# Sheet1.net
KiCad netlist of a schematic drawn in Altium Designer
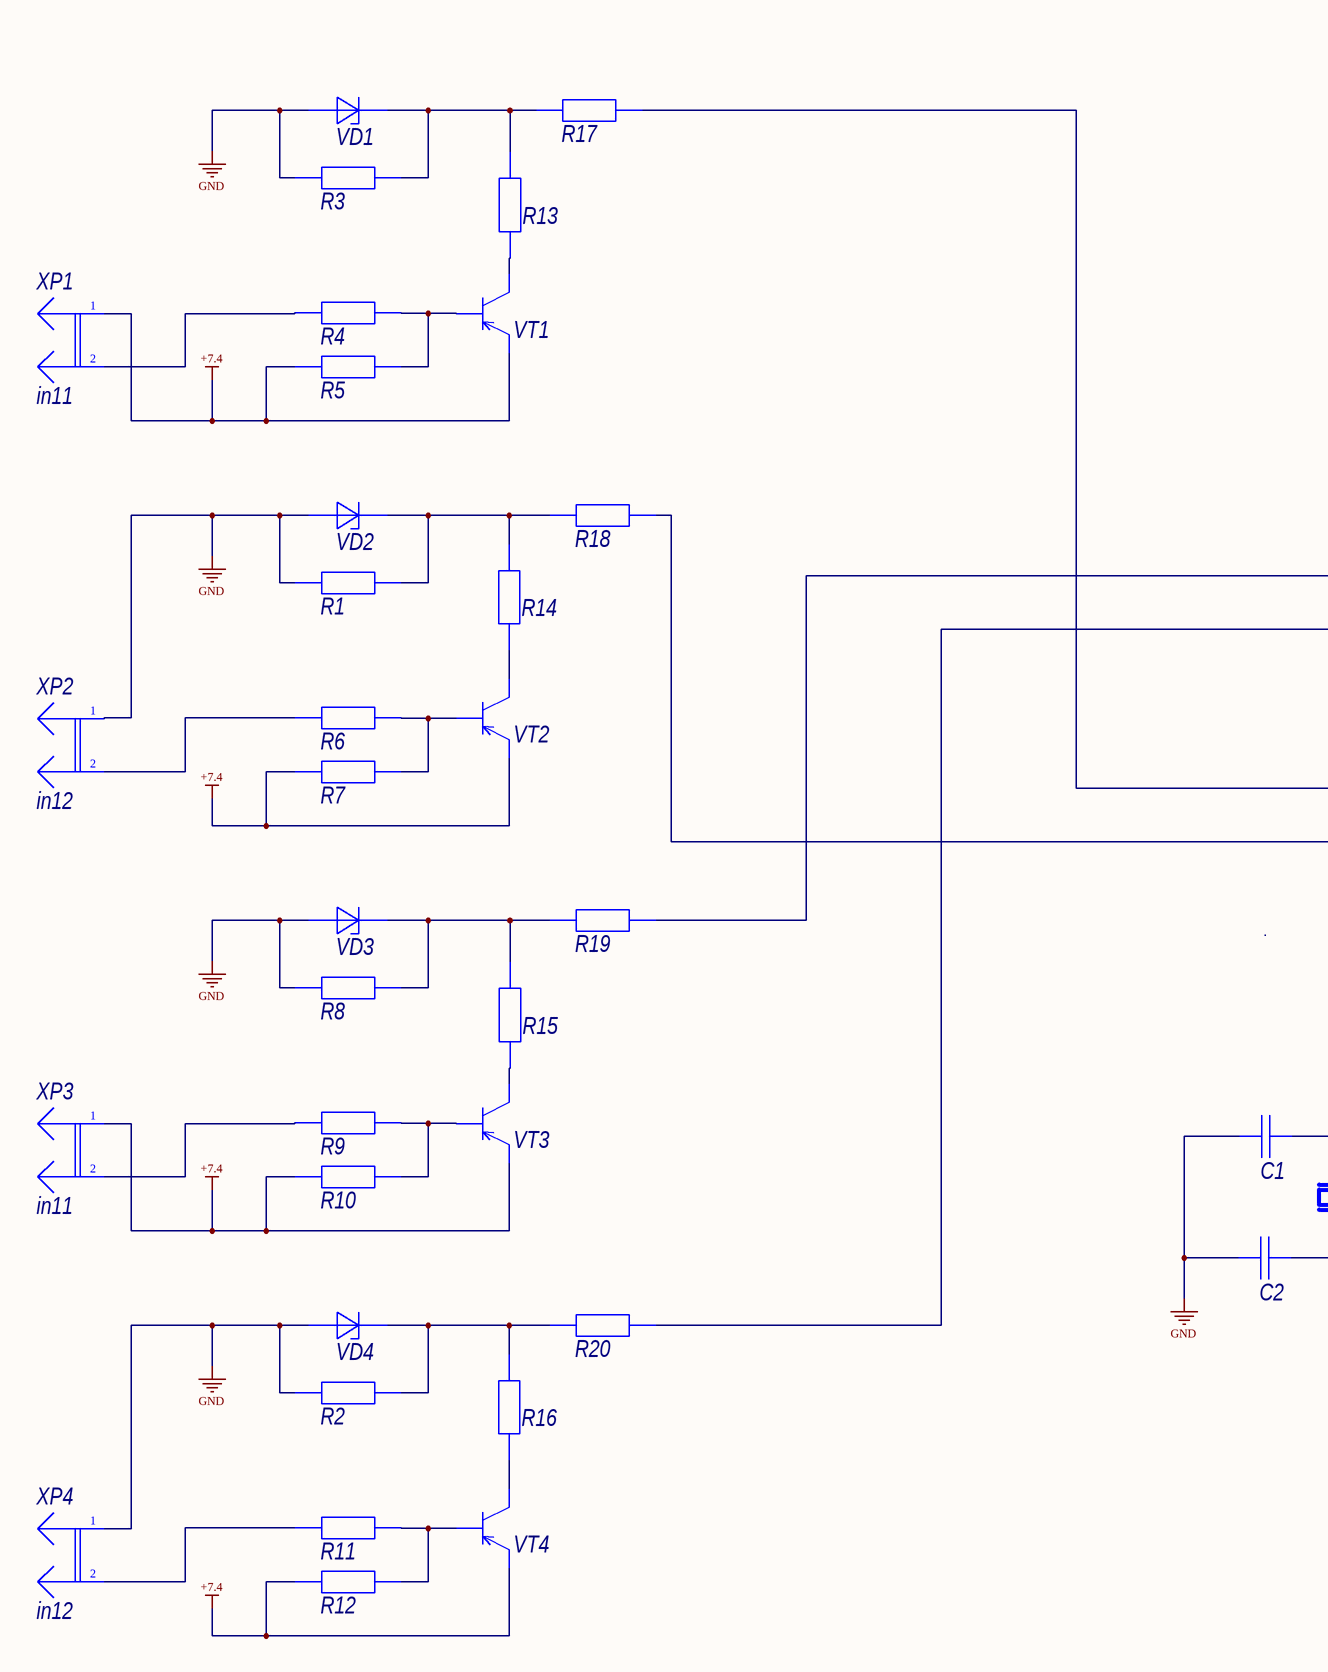
[diagram p0: Sheet1.SchDoc, left]
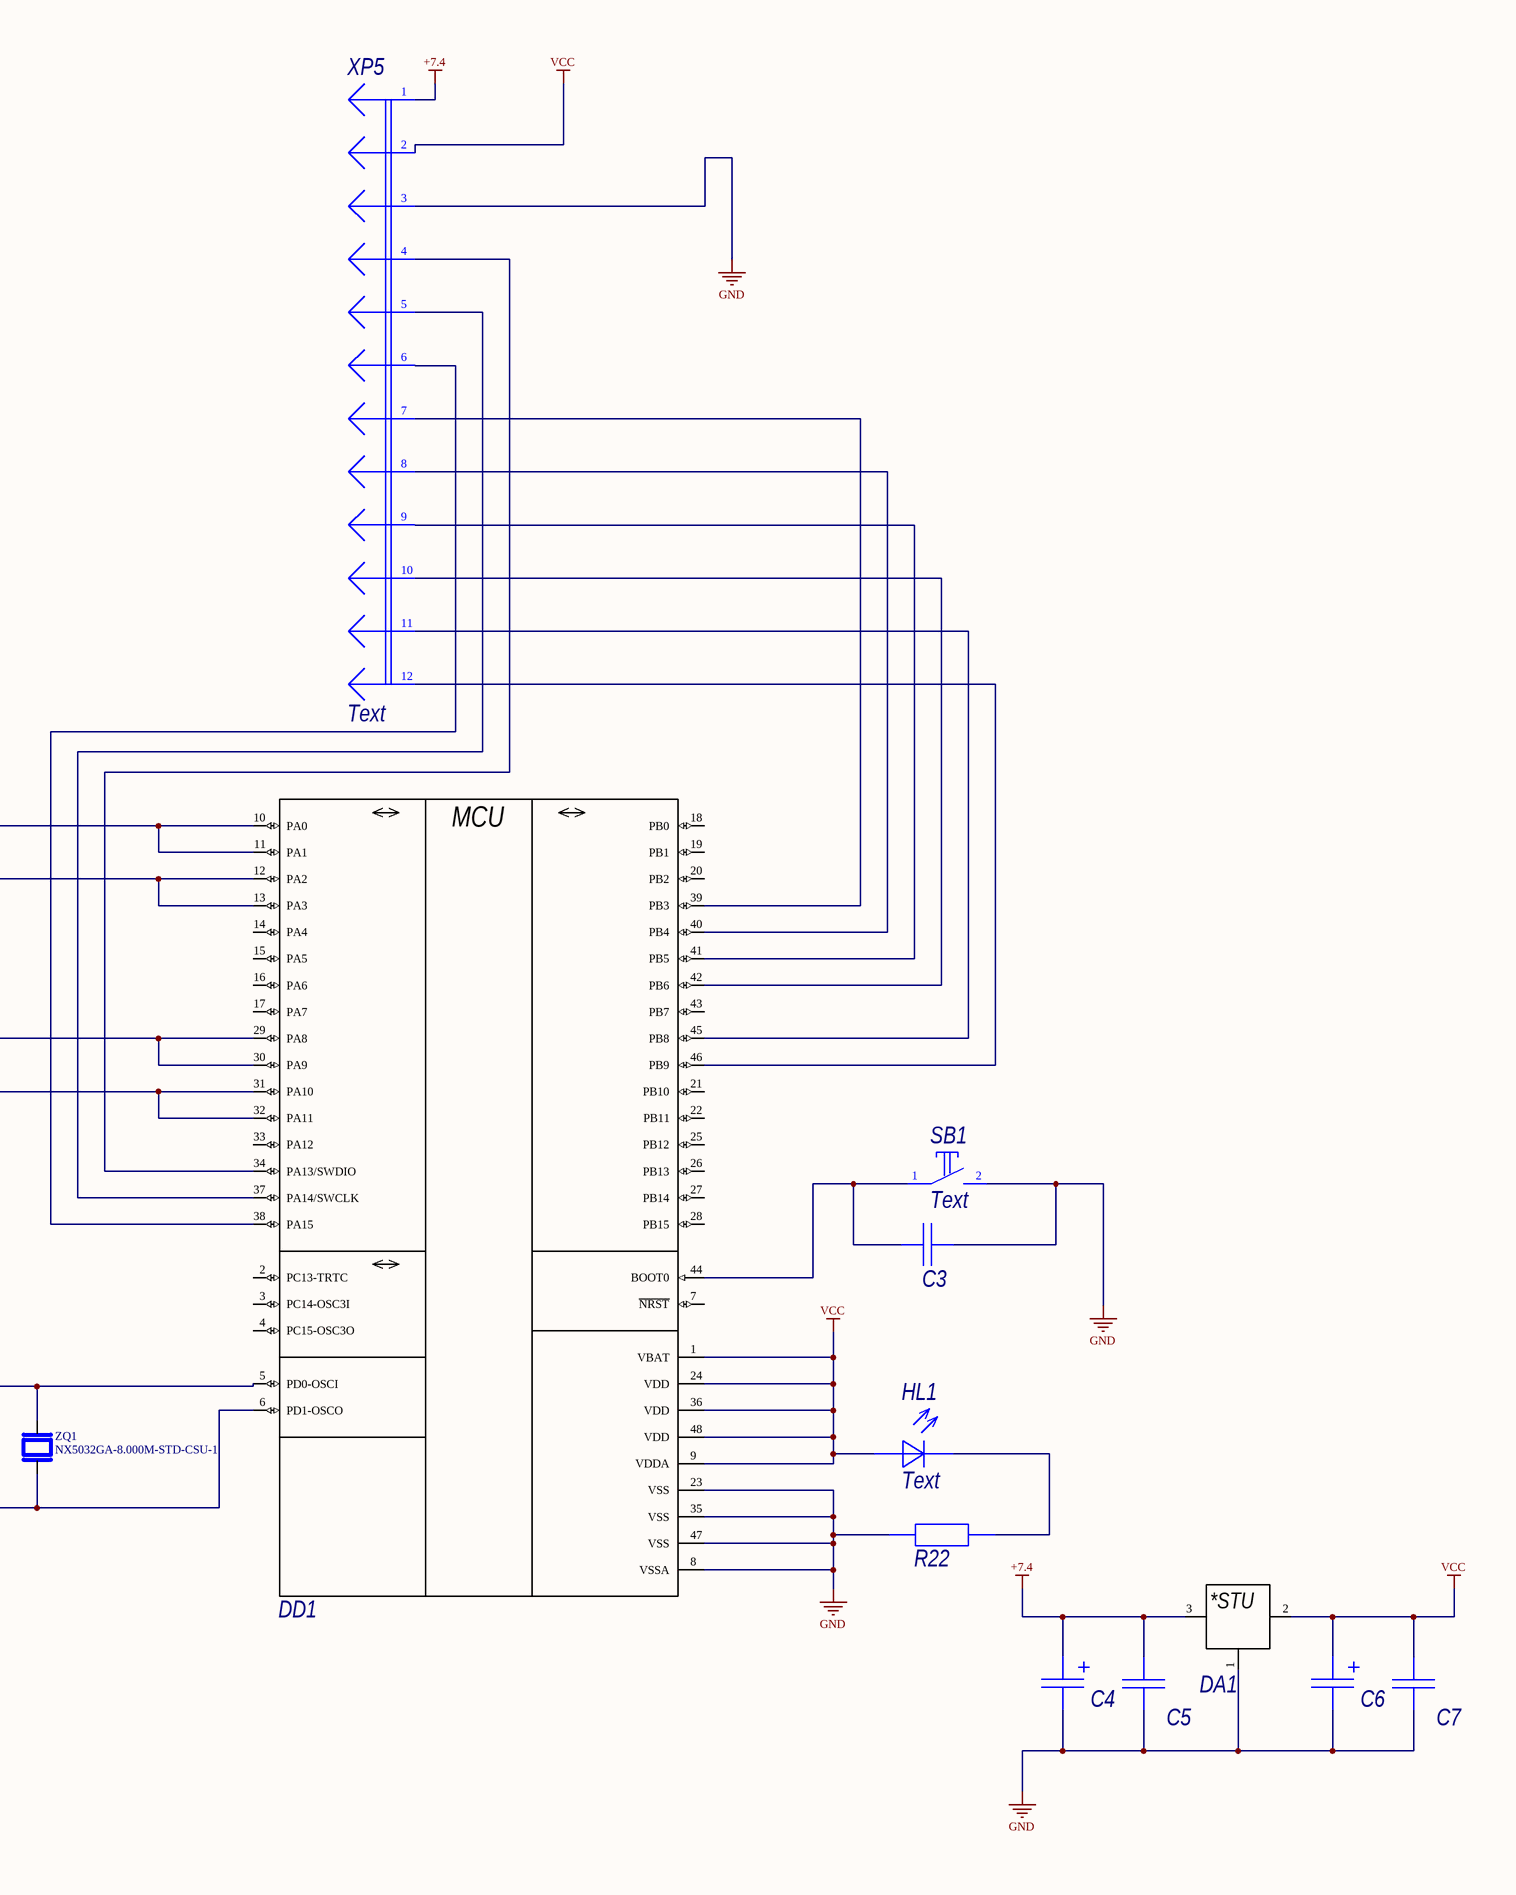
[diagram p1: Sheet1.SchDoc, right]

(export (version "E")
  (design (tool "Eeschema 10.0.6"))
  (components
    (comp (ref "C1")
      (value "Capacitor")
      (footprint "C0603")
      (description "30pF 0603")
      (fields
        (field (name "PART NUMBER") "GRM1885C1H300FA01D")
        (field (name "VOLTAGE") "50V")
        (field (name "PUBLISHER") "Andrew Danich")
      )
      (libsource (lib "Lib_IMP_GOST") (part "Capacitor"))
    )
    (comp (ref "C2")
      (value "Capacitor")
      (footprint "C0603")
      (description "30pF 0603")
      (fields
        (field (name "PART NUMBER") "GRM1885C1H300FA01D")
        (field (name "VOLTAGE") "50V")
        (field (name "PUBLISHER") "Andrew Danich")
      )
      (libsource (lib "Lib_IMP_GOST") (part "Capacitor"))
    )
    (comp (ref "C3")
      (value "Capacitor")
      (footprint "C0603")
      (description "0.1 uF")
      (fields
        (field (name "PART NUMBER") "GRM188R71C104KA01D")
        (field (name "VOLTAGE") "16V")
        (field (name "PUBLISHER") "Andrew Danich")
      )
      (libsource (lib "Lib_IMP_GOST") (part "Capacitor"))
    )
    (comp (ref "C4")
      (value "Capacitor-T")
      (footprint "C3216-p")
      (description "10 uF")
      (fields
        (field (name "PART NUMBER") "T491A106K006AT")
        (field (name "VOLTAGE") "6.3V")
        (field (name "PUBLISHER") "Andrew Danich")
      )
      (libsource (lib "Lib_IMP_GOST") (part "Capacitor-T"))
    )
    (comp (ref "C5")
      (value "Capacitor")
      (footprint "C0603")
      (description "0.1 uF")
      (fields
        (field (name "PART NUMBER") "GRM188R71C104KA01D")
        (field (name "VOLTAGE") "16V")
        (field (name "PUBLISHER") "Andrew Danich")
      )
      (libsource (lib "Lib_IMP_GOST") (part "Capacitor"))
    )
    (comp (ref "C6")
      (value "Capacitor-T")
      (footprint "C3216-p")
      (description "10 uF")
      (fields
        (field (name "PART NUMBER") "T491A106K006AT")
        (field (name "VOLTAGE") "6.3V")
        (field (name "PUBLISHER") "Andrew Danich")
      )
      (libsource (lib "Lib_IMP_GOST") (part "Capacitor-T"))
    )
    (comp (ref "C7")
      (value "Capacitor")
      (footprint "C0603")
      (description "0.1 uF")
      (fields
        (field (name "PART NUMBER") "GRM188R71C104KA01D")
        (field (name "VOLTAGE") "16V")
        (field (name "PUBLISHER") "Andrew Danich")
      )
      (libsource (lib "Lib_IMP_GOST") (part "Capacitor"))
    )
    (comp (ref "DA1")
      (value "LM1117-Series")
      (footprint "SOT-223")
      (fields (field (name "PART NUMBER") "LM1117MPX-ADJ") (field (name "PUBLISHER") "Andrew Danich"))
      (libsource (lib "Lib_IMP_GOST") (part "LM1117-Series"))
    )
    (comp (ref "DD1")
      (value "STM32F103Cxxx-Series")
      (footprint "LQFP-48")
      (fields
        (field (name "PART NUMBER") "STM32F103C8T6")
        (field (name "MANUFACTURER") "STMicroelectronics")
        (field (name "PUBLISHER") "Andrew Danich")
      )
      (libsource (lib "Lib_IMP_GOST") (part "STM32F103Cxxx-Series"))
    )
    (comp (ref "HL1")
      (value "Text")
      (footprint "LD0805")
      (fields
        (field (name "PART NUMBER") "KP-2012SGC")
        (field (name "MANUFACTURER") "Kingbright")
        (field (name "PUBLISHER") "Andrew Danich")
      )
      (libsource (lib "Lib_IMP_GOST") (part "Led-1"))
    )
    (comp (ref "R1")
      (value "Resistor")
      (footprint "R0603")
      (description "10K")
      (fields
        (field (name "PART NUMBER") "RC0603JR-0710KL")
        (field (name "TOLERANCE") "±5%")
        (field (name "PUBLISHER") "Andrew Danich")
      )
      (libsource (lib "Lib_IMP_GOST") (part "Resistor"))
    )
    (comp (ref "R2")
      (value "Resistor")
      (footprint "R0603")
      (description "10K")
      (fields
        (field (name "PART NUMBER") "RC0603JR-0710KL")
        (field (name "TOLERANCE") "±5%")
        (field (name "PUBLISHER") "Andrew Danich")
      )
      (libsource (lib "Lib_IMP_GOST") (part "Resistor"))
    )
    (comp (ref "R3")
      (value "Resistor")
      (footprint "R0603")
      (description "10K")
      (fields
        (field (name "PART NUMBER") "RC0603JR-0710KL")
        (field (name "TOLERANCE") "±5%")
        (field (name "PUBLISHER") "Andrew Danich")
      )
      (libsource (lib "Lib_IMP_GOST") (part "Resistor"))
    )
    (comp (ref "R4")
      (value "Resistor")
      (footprint "R0603")
      (description "10K")
      (fields
        (field (name "PART NUMBER") "RC0603JR-0710KL")
        (field (name "TOLERANCE") "±5%")
        (field (name "PUBLISHER") "Andrew Danich")
      )
      (libsource (lib "Lib_IMP_GOST") (part "Resistor"))
    )
    (comp (ref "R5")
      (value "Resistor")
      (footprint "R0603")
      (description "100k")
      (fields
        (field (name "PART NUMBER") "RC0603JR-07100KL")
        (field (name "TOLERANCE") "±5%")
        (field (name "PUBLISHER") "Andrew Danich")
      )
      (libsource (lib "Lib_IMP_GOST") (part "Resistor"))
    )
    (comp (ref "R6")
      (value "Resistor")
      (footprint "R0603")
      (description "10K")
      (fields
        (field (name "PART NUMBER") "RC0603JR-0710KL")
        (field (name "TOLERANCE") "±5%")
        (field (name "PUBLISHER") "Andrew Danich")
      )
      (libsource (lib "Lib_IMP_GOST") (part "Resistor"))
    )
    (comp (ref "R7")
      (value "Resistor")
      (footprint "R0603")
      (description "10K")
      (fields
        (field (name "PART NUMBER") "RC0603JR-0710KL")
        (field (name "TOLERANCE") "±5%")
        (field (name "PUBLISHER") "Andrew Danich")
      )
      (libsource (lib "Lib_IMP_GOST") (part "Resistor"))
    )
    (comp (ref "R8")
      (value "Resistor")
      (footprint "R0603")
      (description "10K")
      (fields
        (field (name "PART NUMBER") "RC0603JR-0710KL")
        (field (name "TOLERANCE") "±5%")
        (field (name "PUBLISHER") "Andrew Danich")
      )
      (libsource (lib "Lib_IMP_GOST") (part "Resistor"))
    )
    (comp (ref "R9")
      (value "Resistor")
      (footprint "R0603")
      (description "10K")
      (fields
        (field (name "PART NUMBER") "RC0603JR-0710KL")
        (field (name "TOLERANCE") "±5%")
        (field (name "PUBLISHER") "Andrew Danich")
      )
      (libsource (lib "Lib_IMP_GOST") (part "Resistor"))
    )
    (comp (ref "R10")
      (value "Resistor")
      (footprint "R0603")
      (description "100k")
      (fields
        (field (name "PART NUMBER") "RC0603JR-07100KL")
        (field (name "TOLERANCE") "±5%")
        (field (name "PUBLISHER") "Andrew Danich")
      )
      (libsource (lib "Lib_IMP_GOST") (part "Resistor"))
    )
    (comp (ref "R11")
      (value "Resistor")
      (footprint "R0603")
      (description "10K")
      (fields
        (field (name "PART NUMBER") "RC0603JR-0710KL")
        (field (name "TOLERANCE") "±5%")
        (field (name "PUBLISHER") "Andrew Danich")
      )
      (libsource (lib "Lib_IMP_GOST") (part "Resistor"))
    )
    (comp (ref "R12")
      (value "Resistor")
      (footprint "R0603")
      (description "10K")
      (fields
        (field (name "PART NUMBER") "RC0603JR-0710KL")
        (field (name "TOLERANCE") "±5%")
        (field (name "PUBLISHER") "Andrew Danich")
      )
      (libsource (lib "Lib_IMP_GOST") (part "Resistor"))
    )
    (comp (ref "R13")
      (value "Resistor")
      (footprint "R0603")
      (description "1k")
      (fields
        (field (name "PART NUMBER") "RC0603JR-071KL")
        (field (name "TOLERANCE") "±5%")
        (field (name "PUBLISHER") "Andrew Danich")
      )
      (libsource (lib "Lib_IMP_GOST") (part "Resistor"))
    )
    (comp (ref "R14")
      (value "Resistor")
      (footprint "R0603")
      (description "1k")
      (fields
        (field (name "PART NUMBER") "RC0603JR-071KL")
        (field (name "TOLERANCE") "±5%")
        (field (name "PUBLISHER") "Andrew Danich")
      )
      (libsource (lib "Lib_IMP_GOST") (part "Resistor"))
    )
    (comp (ref "R15")
      (value "Resistor")
      (footprint "R0603")
      (description "1k")
      (fields
        (field (name "PART NUMBER") "RC0603JR-071KL")
        (field (name "TOLERANCE") "±5%")
        (field (name "PUBLISHER") "Andrew Danich")
      )
      (libsource (lib "Lib_IMP_GOST") (part "Resistor"))
    )
    (comp (ref "R16")
      (value "Resistor")
      (footprint "R0603")
      (description "1k")
      (fields
        (field (name "PART NUMBER") "RC0603JR-071KL")
        (field (name "TOLERANCE") "±5%")
        (field (name "PUBLISHER") "Andrew Danich")
      )
      (libsource (lib "Lib_IMP_GOST") (part "Resistor"))
    )
    (comp (ref "R17")
      (value "Resistor")
      (footprint "R0603")
      (description "1k")
      (fields
        (field (name "PART NUMBER") "RC0603JR-071KL")
        (field (name "TOLERANCE") "±5%")
        (field (name "PUBLISHER") "Andrew Danich")
      )
      (libsource (lib "Lib_IMP_GOST") (part "Resistor"))
    )
    (comp (ref "R18")
      (value "Resistor")
      (footprint "R0603")
      (description "1k")
      (fields
        (field (name "PART NUMBER") "RC0603JR-071KL")
        (field (name "TOLERANCE") "±5%")
        (field (name "PUBLISHER") "Andrew Danich")
      )
      (libsource (lib "Lib_IMP_GOST") (part "Resistor"))
    )
    (comp (ref "R19")
      (value "Resistor")
      (footprint "R0603")
      (description "1k")
      (fields
        (field (name "PART NUMBER") "RC0603JR-071KL")
        (field (name "TOLERANCE") "±5%")
        (field (name "PUBLISHER") "Andrew Danich")
      )
      (libsource (lib "Lib_IMP_GOST") (part "Resistor"))
    )
    (comp (ref "R20")
      (value "Resistor")
      (footprint "R0603")
      (description "1k")
      (fields
        (field (name "PART NUMBER") "RC0603JR-071KL")
        (field (name "TOLERANCE") "±5%")
        (field (name "PUBLISHER") "Andrew Danich")
      )
      (libsource (lib "Lib_IMP_GOST") (part "Resistor"))
    )
    (comp (ref "R22")
      (value "Resistor")
      (footprint "R0603")
      (description "68 Om")
      (fields
        (field (name "PART NUMBER") "RC0603FR-07200KL")
        (field (name "TOLERANCE") "±1%")
        (field (name "PUBLISHER") "Andrew Danich")
      )
      (libsource (lib "Lib_IMP_GOST") (part "Resistor"))
    )
    (comp (ref "SB1")
      (value "Text")
      (footprint "L-KLS7-TS3303A-1.5-250-B")
      (fields
        (field (name "PART NUMBER") "L-KLS7-TS3303A-1.5-250-B")
        (field (name "PUBLISHER") "Andrew Danich")
      )
      (libsource (lib "Lib_IMP_GOST") (part "L-KLS7-TS3303A-1.5-250-B"))
    )
    (comp (ref "VD1")
      (value "Zener")
      (footprint "SOT-23")
      (fields
        (field (name "PART NUMBER") "BZX84-C3V3")
        (field (name "MANUFACTURER") "NXP")
        (field (name "PUBLISHER") "Andrew Danich")
      )
      (libsource (lib "Lib_IMP_GOST") (part "Zener"))
    )
    (comp (ref "VD2")
      (value "Zener")
      (footprint "SOT-23")
      (fields
        (field (name "PART NUMBER") "BZX84-C3V3")
        (field (name "MANUFACTURER") "NXP")
        (field (name "PUBLISHER") "Andrew Danich")
      )
      (libsource (lib "Lib_IMP_GOST") (part "Zener"))
    )
    (comp (ref "VD3")
      (value "Zener")
      (footprint "SOT-23")
      (fields
        (field (name "PART NUMBER") "BZX84-C3V3")
        (field (name "MANUFACTURER") "NXP")
        (field (name "PUBLISHER") "Andrew Danich")
      )
      (libsource (lib "Lib_IMP_GOST") (part "Zener"))
    )
    (comp (ref "VD4")
      (value "Zener")
      (footprint "SOT-23")
      (fields
        (field (name "PART NUMBER") "BZX84-C3V3")
        (field (name "MANUFACTURER") "NXP")
        (field (name "PUBLISHER") "Andrew Danich")
      )
      (libsource (lib "Lib_IMP_GOST") (part "Zener"))
    )
    (comp (ref "VT1")
      (value "BJT-PNP")
      (footprint "SOT-23")
      (fields (field (name "PART NUMBER") "BC857") (field (name "PUBLISHER") "Andrew Danich"))
      (libsource (lib "Lib_IMP_GOST") (part "BJT-PNP"))
    )
    (comp (ref "VT2")
      (value "BJT-PNP")
      (footprint "SOT-23")
      (fields (field (name "PART NUMBER") "BC857") (field (name "PUBLISHER") "Andrew Danich"))
      (libsource (lib "Lib_IMP_GOST") (part "BJT-PNP"))
    )
    (comp (ref "VT3")
      (value "BJT-PNP")
      (footprint "SOT-23")
      (fields (field (name "PART NUMBER") "BC857") (field (name "PUBLISHER") "Andrew Danich"))
      (libsource (lib "Lib_IMP_GOST") (part "BJT-PNP"))
    )
    (comp (ref "VT4")
      (value "BJT-PNP")
      (footprint "SOT-23")
      (fields (field (name "PART NUMBER") "BC857") (field (name "PUBLISHER") "Andrew Danich"))
      (libsource (lib "Lib_IMP_GOST") (part "BJT-PNP"))
    )
    (comp (ref "XP1")
      (value "in11")
      (footprint "PLS-2")
      (fields (field (name "PART NUMBER") "PLS-2") (field (name "PUBLISHER") "Andrew Danich"))
      (libsource (lib "Lib_IMP_GOST") (part "Con-2-M"))
    )
    (comp (ref "XP2")
      (value "in12")
      (footprint "PLS-2")
      (fields (field (name "PART NUMBER") "PLS-2") (field (name "PUBLISHER") "Andrew Danich"))
      (libsource (lib "Lib_IMP_GOST") (part "Con-2-M"))
    )
    (comp (ref "XP3")
      (value "in11")
      (footprint "PLS-2")
      (fields (field (name "PART NUMBER") "PLS-2") (field (name "PUBLISHER") "Andrew Danich"))
      (libsource (lib "Lib_IMP_GOST") (part "Con-2-M"))
    )
    (comp (ref "XP4")
      (value "in12")
      (footprint "PLS-2")
      (fields (field (name "PART NUMBER") "PLS-2") (field (name "PUBLISHER") "Andrew Danich"))
      (libsource (lib "Lib_IMP_GOST") (part "Con-2-M"))
    )
    (comp (ref "XP5")
      (value "Text")
      (footprint "PLS-12")
      (fields (field (name "PART NUMBER") "PLS-12") (field (name "PUBLISHER") "Andrew Danich"))
      (libsource (lib "Lib_IMP_GOST") (part "Con-12-M"))
    )
    (comp (ref "ZQ1")
      (value "NX5032GA-8.000M-STD-CSU-1")
      (footprint "XTAL_NX5032GA-8.000M-STD-CSU-1")
      (description "8 MHz ±50ppm Crystal 8pF 300 Ohms 2-SMD, No Lead")
      (fields (field (name "MF") "NDK America,"))
      (libsource (lib "NX5032GA-8.000M-STD-CSU-1") (part "NX5032GA-8.000M-STD-CSU-1"))
    )
  )
  (nets
    (net (code "1") (name "+7.4") (class "Default")
      (node (ref "C4") (pin "1") (pinfunction "1_1") (pintype "passive"))
      (node (ref "C5") (pin "1") (pinfunction "1_1") (pintype "passive"))
      (node (ref "DA1") (pin "3") (pinfunction "In_3") (pintype "passive"))
      (node (ref "R10") (pin "1") (pinfunction "1_1") (pintype "passive"))
      (node (ref "R12") (pin "1") (pinfunction "1_1") (pintype "passive"))
      (node (ref "R5") (pin "1") (pinfunction "1_1") (pintype "passive"))
      (node (ref "R7") (pin "1") (pinfunction "1_1") (pintype "passive"))
      (node (ref "VT1") (pin "3") (pinfunction "Э_3") (pintype "passive"))
      (node (ref "VT2") (pin "3") (pinfunction "Э_3") (pintype "passive"))
      (node (ref "VT3") (pin "3") (pinfunction "Э_3") (pintype "passive"))
      (node (ref "VT4") (pin "3") (pinfunction "Э_3") (pintype "passive"))
      (node (ref "XP1") (pin "1") (pintype "passive"))
      (node (ref "XP3") (pin "1") (pintype "passive"))
      (node (ref "XP5") (pin "1") (pintype "passive"))
    )
    (net (code "2") (name "GND") (class "Default")
      (node (ref "C1") (pin "1") (pinfunction "1_1") (pintype "passive"))
      (node (ref "C2") (pin "1") (pinfunction "1_1") (pintype "passive"))
      (node (ref "C3") (pin "2") (pinfunction "2_2") (pintype "passive"))
      (node (ref "C4") (pin "2") (pinfunction "2_2") (pintype "passive"))
      (node (ref "C5") (pin "2") (pinfunction "2_2") (pintype "passive"))
      (node (ref "C6") (pin "2") (pinfunction "2_2") (pintype "passive"))
      (node (ref "C7") (pin "2") (pinfunction "2_2") (pintype "passive"))
      (node (ref "DA1") (pin "1") (pinfunction "Adj/GND_1") (pintype "passive"))
      (node (ref "DD1") (pin "23") (pinfunction "VSS_23") (pintype "power_in"))
      (node (ref "DD1") (pin "35") (pinfunction "VSS_35") (pintype "power_in"))
      (node (ref "DD1") (pin "47") (pinfunction "VSS_47") (pintype "power_in"))
      (node (ref "DD1") (pin "8") (pinfunction "VSSA_8") (pintype "power_in"))
      (node (ref "R1") (pin "1") (pinfunction "1_1") (pintype "passive"))
      (node (ref "R2") (pin "1") (pinfunction "1_1") (pintype "passive"))
      (node (ref "R22") (pin "1") (pinfunction "1_1") (pintype "passive"))
      (node (ref "R3") (pin "1") (pinfunction "1_1") (pintype "passive"))
      (node (ref "R8") (pin "1") (pinfunction "1_1") (pintype "passive"))
      (node (ref "SB1") (pin "2") (pintype "passive"))
      (node (ref "VD1") (pin "1") (pinfunction "А_1") (pintype "passive"))
      (node (ref "VD2") (pin "1") (pinfunction "А_1") (pintype "passive"))
      (node (ref "VD3") (pin "1") (pinfunction "А_1") (pintype "passive"))
      (node (ref "VD4") (pin "1") (pinfunction "А_1") (pintype "passive"))
      (node (ref "XP2") (pin "1") (pintype "passive"))
      (node (ref "XP4") (pin "1") (pintype "passive"))
      (node (ref "XP5") (pin "3") (pintype "passive"))
    )
    (net (code "3") (name "Net-(DD1-BOOT0)") (class "Default")
      (node (ref "C3") (pin "1") (pinfunction "1_1") (pintype "passive"))
      (node (ref "DD1") (pin "44") (pinfunction "BOOT0_44") (pintype "input"))
      (node (ref "SB1") (pin "1") (pintype "passive"))
    )
    (net (code "4") (name "Net-(DD1-PA0)") (class "Default")
      (node (ref "DD1") (pin "10") (pinfunction "PA0_10") (pintype "bidirectional"))
      (node (ref "DD1") (pin "11") (pinfunction "PA1_11") (pintype "bidirectional"))
      (node (ref "R19") (pin "1") (pinfunction "1_1") (pintype "passive"))
    )
    (net (code "5") (name "Net-(DD1-PA2)") (class "Default")
      (node (ref "DD1") (pin "12") (pinfunction "PA2_12") (pintype "bidirectional"))
      (node (ref "DD1") (pin "13") (pinfunction "PA3_13") (pintype "bidirectional"))
      (node (ref "R20") (pin "1") (pinfunction "1_1") (pintype "passive"))
    )
    (net (code "6") (name "Net-(DD1-PA8)") (class "Default")
      (node (ref "DD1") (pin "29") (pinfunction "PA8_29") (pintype "bidirectional"))
      (node (ref "DD1") (pin "30") (pinfunction "PA9_30") (pintype "bidirectional"))
      (node (ref "R17") (pin "1") (pinfunction "1_1") (pintype "passive"))
    )
    (net (code "7") (name "Net-(DD1-PA10)") (class "Default")
      (node (ref "DD1") (pin "31") (pinfunction "PA10_31") (pintype "bidirectional"))
      (node (ref "DD1") (pin "32") (pinfunction "PA11_32") (pintype "bidirectional"))
      (node (ref "R18") (pin "1") (pinfunction "1_1") (pintype "passive"))
    )
    (net (code "8") (name "Net-(DD1-PA13{slash}SWDIO)") (class "Default")
      (node (ref "DD1") (pin "34") (pinfunction "PA13/SWDIO_34") (pintype "bidirectional"))
      (node (ref "XP5") (pin "4") (pintype "passive"))
    )
    (net (code "9") (name "Net-(DD1-PA14{slash}SWCLK)") (class "Default")
      (node (ref "DD1") (pin "37") (pinfunction "PA14/SWCLK_37") (pintype "bidirectional"))
      (node (ref "XP5") (pin "5") (pintype "passive"))
    )
    (net (code "10") (name "Net-(DD1-PA15)") (class "Default")
      (node (ref "DD1") (pin "38") (pinfunction "PA15_38") (pintype "bidirectional"))
      (node (ref "XP5") (pin "6") (pintype "passive"))
    )
    (net (code "11") (name "Net-(DD1-PB3)") (class "Default")
      (node (ref "DD1") (pin "39") (pinfunction "PB3_39") (pintype "bidirectional"))
      (node (ref "XP5") (pin "7") (pintype "passive"))
    )
    (net (code "12") (name "Net-(DD1-PB4)") (class "Default")
      (node (ref "DD1") (pin "40") (pinfunction "PB4_40") (pintype "bidirectional"))
      (node (ref "XP5") (pin "8") (pintype "passive"))
    )
    (net (code "13") (name "Net-(DD1-PB5)") (class "Default")
      (node (ref "DD1") (pin "41") (pinfunction "PB5_41") (pintype "bidirectional"))
      (node (ref "XP5") (pin "9") (pintype "passive"))
    )
    (net (code "14") (name "Net-(DD1-PB6)") (class "Default")
      (node (ref "DD1") (pin "42") (pinfunction "PB6_42") (pintype "bidirectional"))
      (node (ref "XP5") (pin "10") (pintype "passive"))
    )
    (net (code "15") (name "Net-(DD1-PB8)") (class "Default")
      (node (ref "DD1") (pin "45") (pinfunction "PB8_45") (pintype "bidirectional"))
      (node (ref "XP5") (pin "11") (pintype "passive"))
    )
    (net (code "16") (name "Net-(DD1-PB9)") (class "Default")
      (node (ref "DD1") (pin "46") (pinfunction "PB9_46") (pintype "bidirectional"))
      (node (ref "XP5") (pin "12") (pintype "passive"))
    )
    (net (code "17") (name "Net-(DD1-PD0-OSCI)") (class "Default")
      (node (ref "C1") (pin "2") (pinfunction "2_2") (pintype "passive"))
      (node (ref "DD1") (pin "5") (pinfunction "PD0-OSCI_5") (pintype "bidirectional"))
      (node (ref "ZQ1") (pin "2") (pinfunction "2_2") (pintype "passive"))
    )
    (net (code "18") (name "Net-(DD1-PD1-OSCO)") (class "Default")
      (node (ref "C2") (pin "2") (pinfunction "2_2") (pintype "passive"))
      (node (ref "DD1") (pin "6") (pinfunction "PD1-OSCO_6") (pintype "bidirectional"))
      (node (ref "ZQ1") (pin "1") (pinfunction "1_1") (pintype "passive"))
    )
    (net (code "19") (name "Net-(HL1-К)") (class "Default")
      (node (ref "HL1") (pin "2") (pinfunction "К_2") (pintype "passive"))
      (node (ref "R22") (pin "2") (pinfunction "2_2") (pintype "passive"))
    )
    (net (code "20") (name "Net-(R4-Pad1)") (class "Default")
      (node (ref "R4") (pin "1") (pinfunction "1_1") (pintype "passive"))
      (node (ref "XP1") (pin "2") (pintype "passive"))
    )
    (net (code "21") (name "Net-(R6-Pad1)") (class "Default")
      (node (ref "R6") (pin "1") (pinfunction "1_1") (pintype "passive"))
      (node (ref "XP2") (pin "2") (pintype "passive"))
    )
    (net (code "22") (name "Net-(R9-Pad1)") (class "Default")
      (node (ref "R9") (pin "1") (pinfunction "1_1") (pintype "passive"))
      (node (ref "XP3") (pin "2") (pintype "passive"))
    )
    (net (code "23") (name "Net-(R11-Pad1)") (class "Default")
      (node (ref "R11") (pin "1") (pinfunction "1_1") (pintype "passive"))
      (node (ref "XP4") (pin "2") (pintype "passive"))
    )
    (net (code "24") (name "Net-(VD1-К)") (class "Default")
      (node (ref "R13") (pin "1") (pinfunction "1_1") (pintype "passive"))
      (node (ref "R17") (pin "2") (pinfunction "2_2") (pintype "passive"))
      (node (ref "R3") (pin "2") (pinfunction "2_2") (pintype "passive"))
      (node (ref "VD1") (pin "2") (pinfunction "К_2") (pintype "passive"))
    )
    (net (code "25") (name "Net-(VD2-К)") (class "Default")
      (node (ref "R1") (pin "2") (pinfunction "2_2") (pintype "passive"))
      (node (ref "R14") (pin "2") (pinfunction "2_2") (pintype "passive"))
      (node (ref "R18") (pin "2") (pinfunction "2_2") (pintype "passive"))
      (node (ref "VD2") (pin "2") (pinfunction "К_2") (pintype "passive"))
    )
    (net (code "26") (name "Net-(VD3-К)") (class "Default")
      (node (ref "R15") (pin "1") (pinfunction "1_1") (pintype "passive"))
      (node (ref "R19") (pin "2") (pinfunction "2_2") (pintype "passive"))
      (node (ref "R8") (pin "2") (pinfunction "2_2") (pintype "passive"))
      (node (ref "VD3") (pin "2") (pinfunction "К_2") (pintype "passive"))
    )
    (net (code "27") (name "Net-(VD4-К)") (class "Default")
      (node (ref "R16") (pin "2") (pinfunction "2_2") (pintype "passive"))
      (node (ref "R2") (pin "2") (pinfunction "2_2") (pintype "passive"))
      (node (ref "R20") (pin "2") (pinfunction "2_2") (pintype "passive"))
      (node (ref "VD4") (pin "2") (pinfunction "К_2") (pintype "passive"))
    )
    (net (code "28") (name "Net-(VT1-Б)") (class "Default")
      (node (ref "R4") (pin "2") (pinfunction "2_2") (pintype "passive"))
      (node (ref "R5") (pin "2") (pinfunction "2_2") (pintype "passive"))
      (node (ref "VT1") (pin "1") (pinfunction "Б_1") (pintype "passive"))
    )
    (net (code "29") (name "Net-(VT1-К)") (class "Default")
      (node (ref "R13") (pin "2") (pinfunction "2_2") (pintype "passive"))
      (node (ref "VT1") (pin "2") (pinfunction "К_2") (pintype "passive"))
    )
    (net (code "30") (name "Net-(VT2-Б)") (class "Default")
      (node (ref "R6") (pin "2") (pinfunction "2_2") (pintype "passive"))
      (node (ref "R7") (pin "2") (pinfunction "2_2") (pintype "passive"))
      (node (ref "VT2") (pin "1") (pinfunction "Б_1") (pintype "passive"))
    )
    (net (code "31") (name "Net-(VT2-К)") (class "Default")
      (node (ref "R14") (pin "1") (pinfunction "1_1") (pintype "passive"))
      (node (ref "VT2") (pin "2") (pinfunction "К_2") (pintype "passive"))
    )
    (net (code "32") (name "Net-(VT3-Б)") (class "Default")
      (node (ref "R10") (pin "2") (pinfunction "2_2") (pintype "passive"))
      (node (ref "R9") (pin "2") (pinfunction "2_2") (pintype "passive"))
      (node (ref "VT3") (pin "1") (pinfunction "Б_1") (pintype "passive"))
    )
    (net (code "33") (name "Net-(VT3-К)") (class "Default")
      (node (ref "R15") (pin "2") (pinfunction "2_2") (pintype "passive"))
      (node (ref "VT3") (pin "2") (pinfunction "К_2") (pintype "passive"))
    )
    (net (code "34") (name "Net-(VT4-Б)") (class "Default")
      (node (ref "R11") (pin "2") (pinfunction "2_2") (pintype "passive"))
      (node (ref "R12") (pin "2") (pinfunction "2_2") (pintype "passive"))
      (node (ref "VT4") (pin "1") (pinfunction "Б_1") (pintype "passive"))
    )
    (net (code "35") (name "Net-(VT4-К)") (class "Default")
      (node (ref "R16") (pin "1") (pinfunction "1_1") (pintype "passive"))
      (node (ref "VT4") (pin "2") (pinfunction "К_2") (pintype "passive"))
    )
    (net (code "36") (name "VCC") (class "Default")
      (node (ref "C6") (pin "1") (pinfunction "1_1") (pintype "passive"))
      (node (ref "C7") (pin "1") (pinfunction "1_1") (pintype "passive"))
      (node (ref "DA1") (pin "2") (pinfunction "Out_2") (pintype "passive"))
      (node (ref "DD1") (pin "1") (pinfunction "VBAT_1") (pintype "power_in"))
      (node (ref "DD1") (pin "24") (pinfunction "VDD_24") (pintype "power_in"))
      (node (ref "DD1") (pin "36") (pinfunction "VDD_36") (pintype "power_in"))
      (node (ref "DD1") (pin "48") (pinfunction "VDD_48") (pintype "power_in"))
      (node (ref "DD1") (pin "9") (pinfunction "VDDA_9") (pintype "power_in"))
      (node (ref "HL1") (pin "1") (pinfunction "А_1") (pintype "passive"))
      (node (ref "XP5") (pin "2") (pintype "passive"))
    )
    (net (code "37") (name "unconnected-(DD1-PA4-Pad14)") (class "Default")
      (node (ref "DD1") (pin "14") (pinfunction "PA4_14") (pintype "bidirectional"))
    )
    (net (code "38") (name "unconnected-(DD1-PA5-Pad15)") (class "Default")
      (node (ref "DD1") (pin "15") (pinfunction "PA5_15") (pintype "bidirectional"))
    )
    (net (code "39") (name "unconnected-(DD1-PA6-Pad16)") (class "Default")
      (node (ref "DD1") (pin "16") (pinfunction "PA6_16") (pintype "bidirectional"))
    )
    (net (code "40") (name "unconnected-(DD1-PA7-Pad17)") (class "Default")
      (node (ref "DD1") (pin "17") (pinfunction "PA7_17") (pintype "bidirectional"))
    )
    (net (code "41") (name "unconnected-(DD1-PA12-Pad33)") (class "Default")
      (node (ref "DD1") (pin "33") (pinfunction "PA12_33") (pintype "bidirectional"))
    )
    (net (code "42") (name "unconnected-(DD1-PB0-Pad18)") (class "Default")
      (node (ref "DD1") (pin "18") (pinfunction "PB0_18") (pintype "bidirectional"))
    )
    (net (code "43") (name "unconnected-(DD1-PB1-Pad19)") (class "Default")
      (node (ref "DD1") (pin "19") (pinfunction "PB1_19") (pintype "bidirectional"))
    )
    (net (code "44") (name "unconnected-(DD1-PB2-Pad20)") (class "Default")
      (node (ref "DD1") (pin "20") (pinfunction "PB2_20") (pintype "bidirectional"))
    )
    (net (code "45") (name "unconnected-(DD1-PB7-Pad43)") (class "Default")
      (node (ref "DD1") (pin "43") (pinfunction "PB7_43") (pintype "bidirectional"))
    )
    (net (code "46") (name "unconnected-(DD1-PB10-Pad21)") (class "Default")
      (node (ref "DD1") (pin "21") (pinfunction "PB10_21") (pintype "bidirectional"))
    )
    (net (code "47") (name "unconnected-(DD1-PB11-Pad22)") (class "Default")
      (node (ref "DD1") (pin "22") (pinfunction "PB11_22") (pintype "bidirectional"))
    )
    (net (code "48") (name "unconnected-(DD1-PB12-Pad25)") (class "Default")
      (node (ref "DD1") (pin "25") (pinfunction "PB12_25") (pintype "bidirectional"))
    )
    (net (code "49") (name "unconnected-(DD1-PB13-Pad26)") (class "Default")
      (node (ref "DD1") (pin "26") (pinfunction "PB13_26") (pintype "bidirectional"))
    )
    (net (code "50") (name "unconnected-(DD1-PB14-Pad27)") (class "Default")
      (node (ref "DD1") (pin "27") (pinfunction "PB14_27") (pintype "bidirectional"))
    )
    (net (code "51") (name "unconnected-(DD1-PB15-Pad28)") (class "Default")
      (node (ref "DD1") (pin "28") (pinfunction "PB15_28") (pintype "bidirectional"))
    )
    (net (code "52") (name "unconnected-(DD1-PC13-TRTC-Pad2)") (class "Default")
      (node (ref "DD1") (pin "2") (pinfunction "PC13-TRTC_2") (pintype "bidirectional"))
    )
    (net (code "53") (name "unconnected-(DD1-PC14-OSC3I-Pad3)") (class "Default")
      (node (ref "DD1") (pin "3") (pinfunction "PC14-OSC3I_3") (pintype "bidirectional"))
    )
    (net (code "54") (name "unconnected-(DD1-PC15-OSC3O-Pad4)") (class "Default")
      (node (ref "DD1") (pin "4") (pinfunction "PC15-OSC3O_4") (pintype "bidirectional"))
    )
    (net (code "55") (name "unconnected-(DD1-~{NRST}-Pad7)") (class "Default")
      (node (ref "DD1") (pin "7") (pinfunction "~{NRST}_7") (pintype "bidirectional"))
    )
  )
)
